# 737NG_MCDU_MainPanel_v_01.net
KiCad netlist of a schematic drawn in EasyEDA
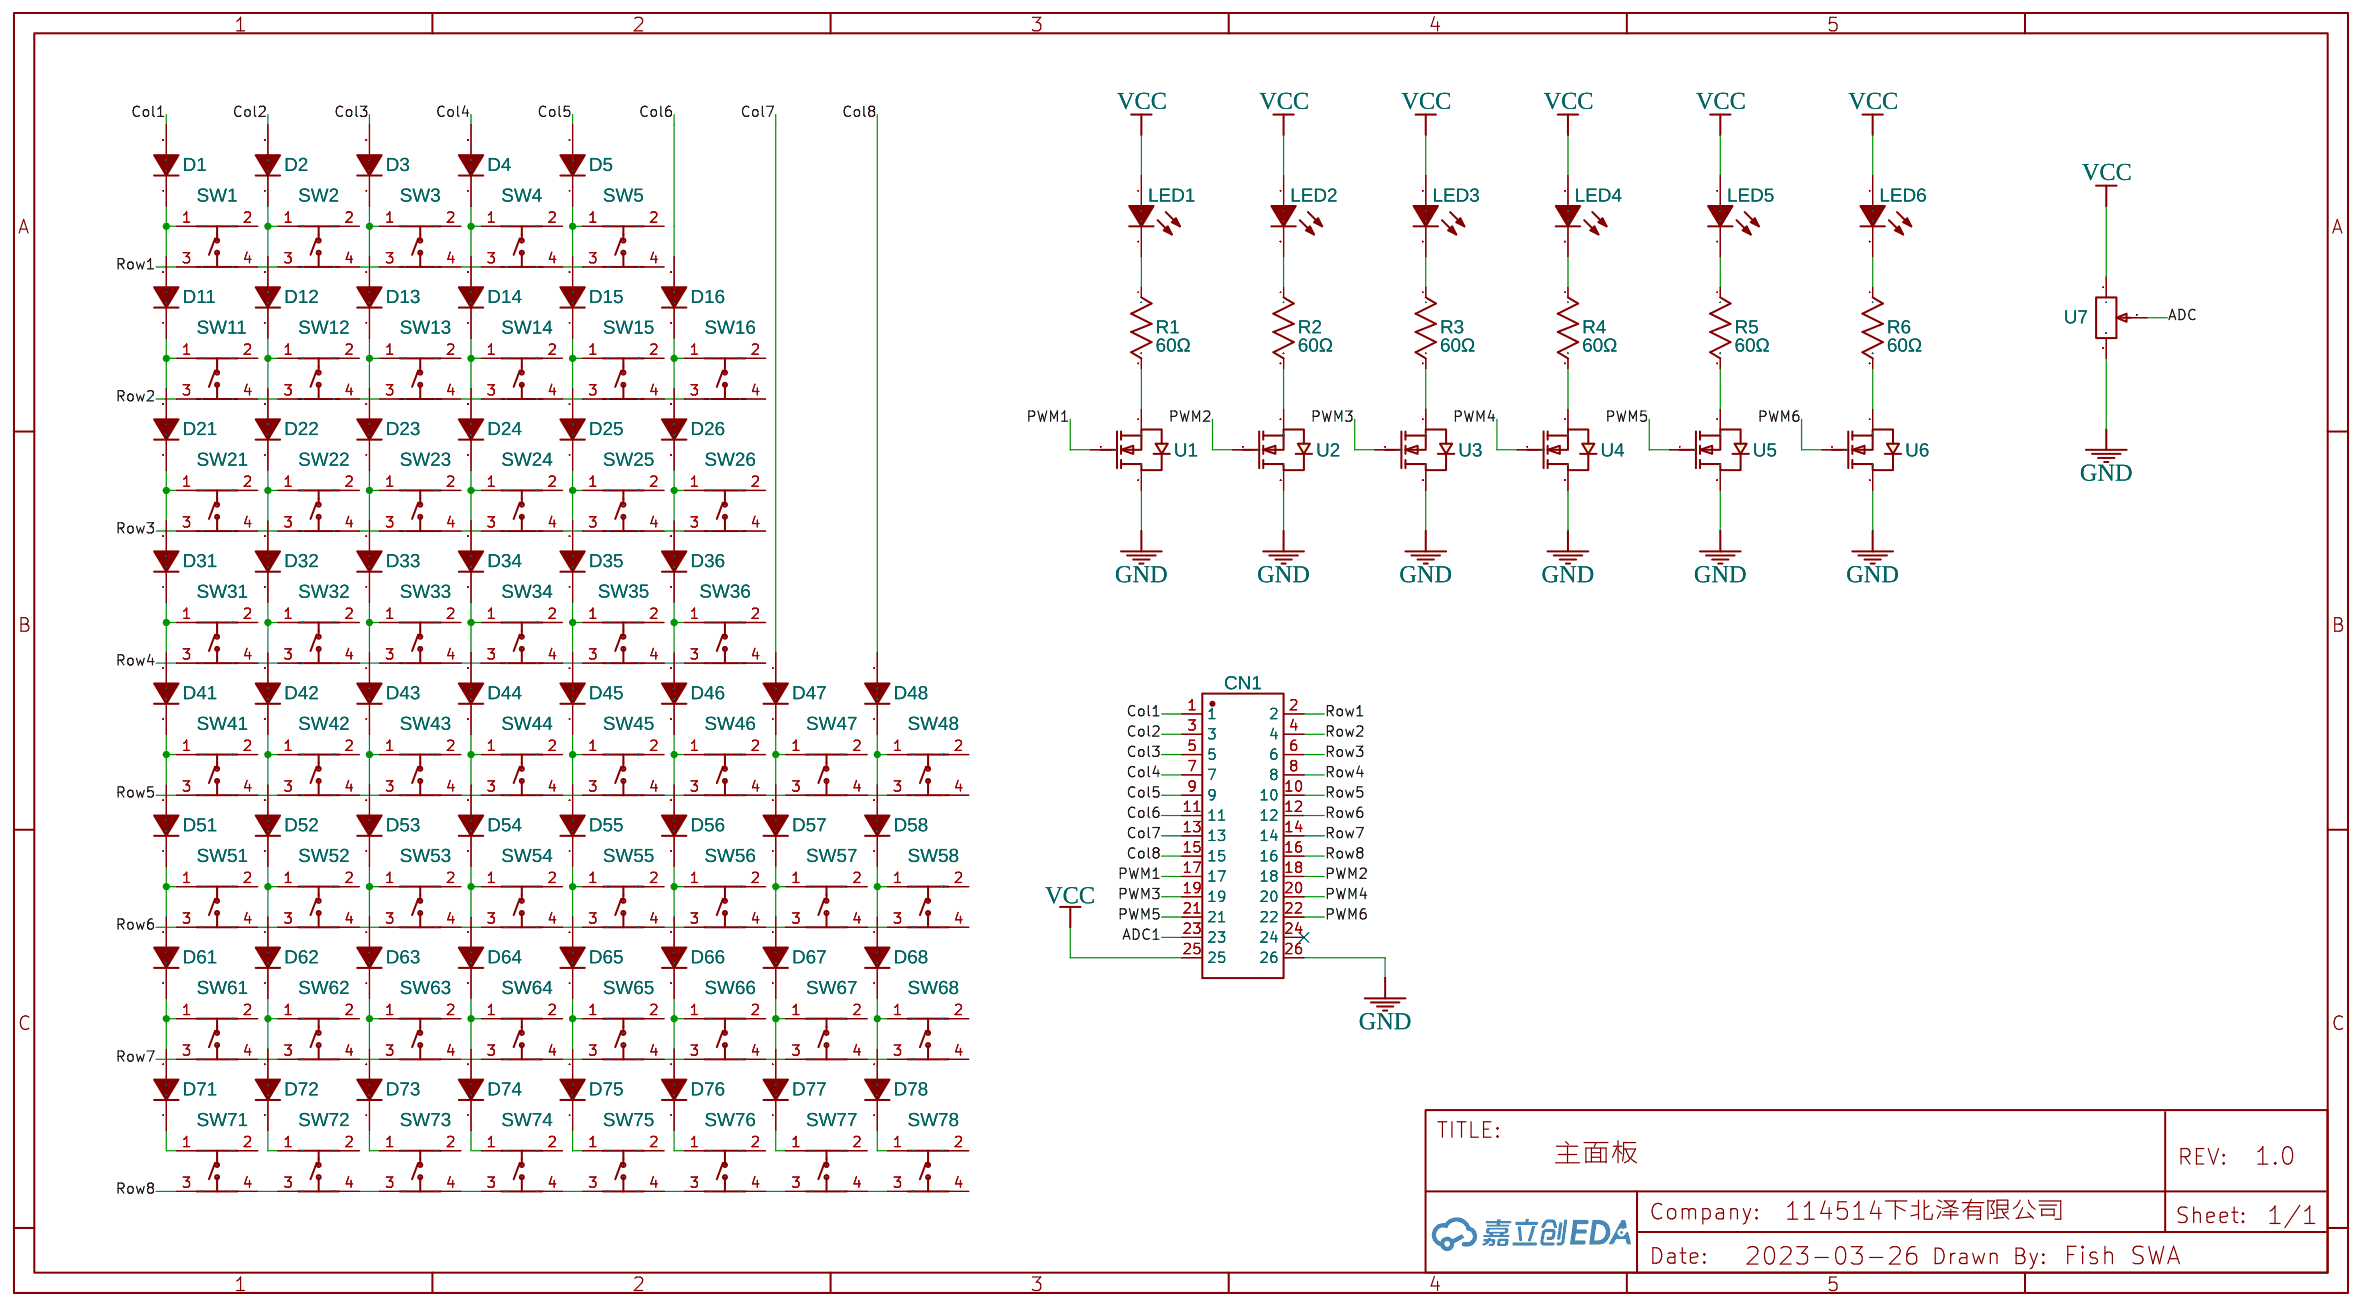
[diagram p0: schematic sheet]

(export (version "E")
  (design (tool "Eeschema 10.0.6"))
  (components
    (comp (ref "CN1")
      (value "A2004WV-2X13P")
      (fields (field (name "BOM_Supplier Part") "C465323"))
      (libsource (lib "") (part "A2004WV-2X13P"))
    )
    (comp (ref "D1")
      (value "1N4148WS T4")
      (fields (field (name "BOM_Manufacturer Part") "1N4148WS") (field (name "BOM_Supplier Part") "C2128"))
      (libsource (lib "") (part "1N4148WS T4"))
    )
    (comp (ref "D2")
      (value "1N4148WS T4")
      (fields (field (name "BOM_Manufacturer Part") "1N4148WS") (field (name "BOM_Supplier Part") "C2128"))
      (libsource (lib "") (part "1N4148WS T4"))
    )
    (comp (ref "D3")
      (value "1N4148WS T4")
      (fields (field (name "BOM_Manufacturer Part") "1N4148WS") (field (name "BOM_Supplier Part") "C2128"))
      (libsource (lib "") (part "1N4148WS T4"))
    )
    (comp (ref "D4")
      (value "1N4148WS T4")
      (fields (field (name "BOM_Manufacturer Part") "1N4148WS") (field (name "BOM_Supplier Part") "C2128"))
      (libsource (lib "") (part "1N4148WS T4"))
    )
    (comp (ref "D5")
      (value "1N4148WS T4")
      (fields (field (name "BOM_Manufacturer Part") "1N4148WS") (field (name "BOM_Supplier Part") "C2128"))
      (libsource (lib "") (part "1N4148WS T4"))
    )
    (comp (ref "D11")
      (value "1N4148WS T4")
      (fields (field (name "BOM_Manufacturer Part") "1N4148WS") (field (name "BOM_Supplier Part") "C2128"))
      (libsource (lib "") (part "1N4148WS T4"))
    )
    (comp (ref "D12")
      (value "1N4148WS T4")
      (fields (field (name "BOM_Manufacturer Part") "1N4148WS") (field (name "BOM_Supplier Part") "C2128"))
      (libsource (lib "") (part "1N4148WS T4"))
    )
    (comp (ref "D13")
      (value "1N4148WS T4")
      (fields (field (name "BOM_Manufacturer Part") "1N4148WS") (field (name "BOM_Supplier Part") "C2128"))
      (libsource (lib "") (part "1N4148WS T4"))
    )
    (comp (ref "D14")
      (value "1N4148WS T4")
      (fields (field (name "BOM_Manufacturer Part") "1N4148WS") (field (name "BOM_Supplier Part") "C2128"))
      (libsource (lib "") (part "1N4148WS T4"))
    )
    (comp (ref "D15")
      (value "1N4148WS T4")
      (fields (field (name "BOM_Manufacturer Part") "1N4148WS") (field (name "BOM_Supplier Part") "C2128"))
      (libsource (lib "") (part "1N4148WS T4"))
    )
    (comp (ref "D16")
      (value "1N4148WS T4")
      (fields (field (name "BOM_Manufacturer Part") "1N4148WS") (field (name "BOM_Supplier Part") "C2128"))
      (libsource (lib "") (part "1N4148WS T4"))
    )
    (comp (ref "D21")
      (value "1N4148WS T4")
      (fields (field (name "BOM_Manufacturer Part") "1N4148WS") (field (name "BOM_Supplier Part") "C2128"))
      (libsource (lib "") (part "1N4148WS T4"))
    )
    (comp (ref "D22")
      (value "1N4148WS T4")
      (fields (field (name "BOM_Manufacturer Part") "1N4148WS") (field (name "BOM_Supplier Part") "C2128"))
      (libsource (lib "") (part "1N4148WS T4"))
    )
    (comp (ref "D23")
      (value "1N4148WS T4")
      (fields (field (name "BOM_Manufacturer Part") "1N4148WS") (field (name "BOM_Supplier Part") "C2128"))
      (libsource (lib "") (part "1N4148WS T4"))
    )
    (comp (ref "D24")
      (value "1N4148WS T4")
      (fields (field (name "BOM_Manufacturer Part") "1N4148WS") (field (name "BOM_Supplier Part") "C2128"))
      (libsource (lib "") (part "1N4148WS T4"))
    )
    (comp (ref "D25")
      (value "1N4148WS T4")
      (fields (field (name "BOM_Manufacturer Part") "1N4148WS") (field (name "BOM_Supplier Part") "C2128"))
      (libsource (lib "") (part "1N4148WS T4"))
    )
    (comp (ref "D26")
      (value "1N4148WS T4")
      (fields (field (name "BOM_Manufacturer Part") "1N4148WS") (field (name "BOM_Supplier Part") "C2128"))
      (libsource (lib "") (part "1N4148WS T4"))
    )
    (comp (ref "D31")
      (value "1N4148WS T4")
      (fields (field (name "BOM_Manufacturer Part") "1N4148WS") (field (name "BOM_Supplier Part") "C2128"))
      (libsource (lib "") (part "1N4148WS T4"))
    )
    (comp (ref "D32")
      (value "1N4148WS T4")
      (fields (field (name "BOM_Manufacturer Part") "1N4148WS") (field (name "BOM_Supplier Part") "C2128"))
      (libsource (lib "") (part "1N4148WS T4"))
    )
    (comp (ref "D33")
      (value "1N4148WS T4")
      (fields (field (name "BOM_Manufacturer Part") "1N4148WS") (field (name "BOM_Supplier Part") "C2128"))
      (libsource (lib "") (part "1N4148WS T4"))
    )
    (comp (ref "D34")
      (value "1N4148WS T4")
      (fields (field (name "BOM_Manufacturer Part") "1N4148WS") (field (name "BOM_Supplier Part") "C2128"))
      (libsource (lib "") (part "1N4148WS T4"))
    )
    (comp (ref "D35")
      (value "1N4148WS T4")
      (fields (field (name "BOM_Manufacturer Part") "1N4148WS") (field (name "BOM_Supplier Part") "C2128"))
      (libsource (lib "") (part "1N4148WS T4"))
    )
    (comp (ref "D36")
      (value "1N4148WS T4")
      (fields (field (name "BOM_Manufacturer Part") "1N4148WS") (field (name "BOM_Supplier Part") "C2128"))
      (libsource (lib "") (part "1N4148WS T4"))
    )
    (comp (ref "D41")
      (value "1N4148WS T4")
      (fields (field (name "BOM_Manufacturer Part") "1N4148WS") (field (name "BOM_Supplier Part") "C2128"))
      (libsource (lib "") (part "1N4148WS T4"))
    )
    (comp (ref "D42")
      (value "1N4148WS T4")
      (fields (field (name "BOM_Manufacturer Part") "1N4148WS") (field (name "BOM_Supplier Part") "C2128"))
      (libsource (lib "") (part "1N4148WS T4"))
    )
    (comp (ref "D43")
      (value "1N4148WS T4")
      (fields (field (name "BOM_Manufacturer Part") "1N4148WS") (field (name "BOM_Supplier Part") "C2128"))
      (libsource (lib "") (part "1N4148WS T4"))
    )
    (comp (ref "D44")
      (value "1N4148WS T4")
      (fields (field (name "BOM_Manufacturer Part") "1N4148WS") (field (name "BOM_Supplier Part") "C2128"))
      (libsource (lib "") (part "1N4148WS T4"))
    )
    (comp (ref "D45")
      (value "1N4148WS T4")
      (fields (field (name "BOM_Manufacturer Part") "1N4148WS") (field (name "BOM_Supplier Part") "C2128"))
      (libsource (lib "") (part "1N4148WS T4"))
    )
    (comp (ref "D46")
      (value "1N4148WS T4")
      (fields (field (name "BOM_Manufacturer Part") "1N4148WS") (field (name "BOM_Supplier Part") "C2128"))
      (libsource (lib "") (part "1N4148WS T4"))
    )
    (comp (ref "D47")
      (value "1N4148WS T4")
      (fields (field (name "BOM_Manufacturer Part") "1N4148WS") (field (name "BOM_Supplier Part") "C2128"))
      (libsource (lib "") (part "1N4148WS T4"))
    )
    (comp (ref "D48")
      (value "1N4148WS T4")
      (fields (field (name "BOM_Manufacturer Part") "1N4148WS") (field (name "BOM_Supplier Part") "C2128"))
      (libsource (lib "") (part "1N4148WS T4"))
    )
    (comp (ref "D51")
      (value "1N4148WS T4")
      (fields (field (name "BOM_Manufacturer Part") "1N4148WS") (field (name "BOM_Supplier Part") "C2128"))
      (libsource (lib "") (part "1N4148WS T4"))
    )
    (comp (ref "D52")
      (value "1N4148WS T4")
      (fields (field (name "BOM_Manufacturer Part") "1N4148WS") (field (name "BOM_Supplier Part") "C2128"))
      (libsource (lib "") (part "1N4148WS T4"))
    )
    (comp (ref "D53")
      (value "1N4148WS T4")
      (fields (field (name "BOM_Manufacturer Part") "1N4148WS") (field (name "BOM_Supplier Part") "C2128"))
      (libsource (lib "") (part "1N4148WS T4"))
    )
    (comp (ref "D54")
      (value "1N4148WS T4")
      (fields (field (name "BOM_Manufacturer Part") "1N4148WS") (field (name "BOM_Supplier Part") "C2128"))
      (libsource (lib "") (part "1N4148WS T4"))
    )
    (comp (ref "D55")
      (value "1N4148WS T4")
      (fields (field (name "BOM_Manufacturer Part") "1N4148WS") (field (name "BOM_Supplier Part") "C2128"))
      (libsource (lib "") (part "1N4148WS T4"))
    )
    (comp (ref "D56")
      (value "1N4148WS T4")
      (fields (field (name "BOM_Manufacturer Part") "1N4148WS") (field (name "BOM_Supplier Part") "C2128"))
      (libsource (lib "") (part "1N4148WS T4"))
    )
    (comp (ref "D57")
      (value "1N4148WS T4")
      (fields (field (name "BOM_Manufacturer Part") "1N4148WS") (field (name "BOM_Supplier Part") "C2128"))
      (libsource (lib "") (part "1N4148WS T4"))
    )
    (comp (ref "D58")
      (value "1N4148WS T4")
      (fields (field (name "BOM_Manufacturer Part") "1N4148WS") (field (name "BOM_Supplier Part") "C2128"))
      (libsource (lib "") (part "1N4148WS T4"))
    )
    (comp (ref "D61")
      (value "1N4148WS T4")
      (fields (field (name "BOM_Manufacturer Part") "1N4148WS") (field (name "BOM_Supplier Part") "C2128"))
      (libsource (lib "") (part "1N4148WS T4"))
    )
    (comp (ref "D62")
      (value "1N4148WS T4")
      (fields (field (name "BOM_Manufacturer Part") "1N4148WS") (field (name "BOM_Supplier Part") "C2128"))
      (libsource (lib "") (part "1N4148WS T4"))
    )
    (comp (ref "D63")
      (value "1N4148WS T4")
      (fields (field (name "BOM_Manufacturer Part") "1N4148WS") (field (name "BOM_Supplier Part") "C2128"))
      (libsource (lib "") (part "1N4148WS T4"))
    )
    (comp (ref "D64")
      (value "1N4148WS T4")
      (fields (field (name "BOM_Manufacturer Part") "1N4148WS") (field (name "BOM_Supplier Part") "C2128"))
      (libsource (lib "") (part "1N4148WS T4"))
    )
    (comp (ref "D65")
      (value "1N4148WS T4")
      (fields (field (name "BOM_Manufacturer Part") "1N4148WS") (field (name "BOM_Supplier Part") "C2128"))
      (libsource (lib "") (part "1N4148WS T4"))
    )
    (comp (ref "D66")
      (value "1N4148WS T4")
      (fields (field (name "BOM_Manufacturer Part") "1N4148WS") (field (name "BOM_Supplier Part") "C2128"))
      (libsource (lib "") (part "1N4148WS T4"))
    )
    (comp (ref "D67")
      (value "1N4148WS T4")
      (fields (field (name "BOM_Manufacturer Part") "1N4148WS") (field (name "BOM_Supplier Part") "C2128"))
      (libsource (lib "") (part "1N4148WS T4"))
    )
    (comp (ref "D68")
      (value "1N4148WS T4")
      (fields (field (name "BOM_Manufacturer Part") "1N4148WS") (field (name "BOM_Supplier Part") "C2128"))
      (libsource (lib "") (part "1N4148WS T4"))
    )
    (comp (ref "D71")
      (value "1N4148WS T4")
      (fields (field (name "BOM_Manufacturer Part") "1N4148WS") (field (name "BOM_Supplier Part") "C2128"))
      (libsource (lib "") (part "1N4148WS T4"))
    )
    (comp (ref "D72")
      (value "1N4148WS T4")
      (fields (field (name "BOM_Manufacturer Part") "1N4148WS") (field (name "BOM_Supplier Part") "C2128"))
      (libsource (lib "") (part "1N4148WS T4"))
    )
    (comp (ref "D73")
      (value "1N4148WS T4")
      (fields (field (name "BOM_Manufacturer Part") "1N4148WS") (field (name "BOM_Supplier Part") "C2128"))
      (libsource (lib "") (part "1N4148WS T4"))
    )
    (comp (ref "D74")
      (value "1N4148WS T4")
      (fields (field (name "BOM_Manufacturer Part") "1N4148WS") (field (name "BOM_Supplier Part") "C2128"))
      (libsource (lib "") (part "1N4148WS T4"))
    )
    (comp (ref "D75")
      (value "1N4148WS T4")
      (fields (field (name "BOM_Manufacturer Part") "1N4148WS") (field (name "BOM_Supplier Part") "C2128"))
      (libsource (lib "") (part "1N4148WS T4"))
    )
    (comp (ref "D76")
      (value "1N4148WS T4")
      (fields (field (name "BOM_Manufacturer Part") "1N4148WS") (field (name "BOM_Supplier Part") "C2128"))
      (libsource (lib "") (part "1N4148WS T4"))
    )
    (comp (ref "D77")
      (value "1N4148WS T4")
      (fields (field (name "BOM_Manufacturer Part") "1N4148WS") (field (name "BOM_Supplier Part") "C2128"))
      (libsource (lib "") (part "1N4148WS T4"))
    )
    (comp (ref "D78")
      (value "1N4148WS T4")
      (fields (field (name "BOM_Manufacturer Part") "1N4148WS") (field (name "BOM_Supplier Part") "C2128"))
      (libsource (lib "") (part "1N4148WS T4"))
    )
    (comp (ref "LED1")
      (value "SML-H12P8TT86")
      (fields (field (name "BOM_Supplier Part") "C510035"))
      (libsource (lib "") (part "SML-H12P8TT86"))
    )
    (comp (ref "LED2")
      (value "SML-H12P8TT86")
      (fields (field (name "BOM_Supplier Part") "C510035"))
      (libsource (lib "") (part "SML-H12P8TT86"))
    )
    (comp (ref "LED3")
      (value "SML-H12P8TT86")
      (fields (field (name "BOM_Supplier Part") "C510035"))
      (libsource (lib "") (part "SML-H12P8TT86"))
    )
    (comp (ref "LED4")
      (value "SML-H12P8TT86")
      (fields (field (name "BOM_Supplier Part") "C510035"))
      (libsource (lib "") (part "SML-H12P8TT86"))
    )
    (comp (ref "LED5")
      (value "SML-H12P8TT86")
      (fields (field (name "BOM_Supplier Part") "C510035"))
      (libsource (lib "") (part "SML-H12P8TT86"))
    )
    (comp (ref "LED6")
      (value "SML-H12P8TT86")
      (fields (field (name "BOM_Supplier Part") "C510035"))
      (libsource (lib "") (part "SML-H12P8TT86"))
    )
    (comp (ref "R1") (value "60Ω") (libsource (lib "") (part "R_0805_US")))
    (comp (ref "R2") (value "60Ω") (libsource (lib "") (part "R_0805_US")))
    (comp (ref "R3") (value "60Ω") (libsource (lib "") (part "R_0805_US")))
    (comp (ref "R4") (value "60Ω") (libsource (lib "") (part "R_0805_US")))
    (comp (ref "R5") (value "60Ω") (libsource (lib "") (part "R_0805_US")))
    (comp (ref "R6") (value "60Ω") (libsource (lib "") (part "R_0805_US")))
    (comp (ref "SW1")
      (value "PTS525SM15SMTR2LFS")
      (fields (field (name "BOM_Supplier Part") "C221856"))
      (libsource (lib "") (part "PTS525SM15SMTR2LFS"))
    )
    (comp (ref "SW2")
      (value "PTS525SM15SMTR2LFS")
      (fields (field (name "BOM_Supplier Part") "C221856"))
      (libsource (lib "") (part "PTS525SM15SMTR2LFS"))
    )
    (comp (ref "SW3")
      (value "PTS525SM15SMTR2LFS")
      (fields (field (name "BOM_Supplier Part") "C221856"))
      (libsource (lib "") (part "PTS525SM15SMTR2LFS"))
    )
    (comp (ref "SW4")
      (value "PTS525SM15SMTR2LFS")
      (fields (field (name "BOM_Supplier Part") "C221856"))
      (libsource (lib "") (part "PTS525SM15SMTR2LFS"))
    )
    (comp (ref "SW5")
      (value "PTS525SM15SMTR2LFS")
      (fields (field (name "BOM_Supplier Part") "C221856"))
      (libsource (lib "") (part "PTS525SM15SMTR2LFS"))
    )
    (comp (ref "SW11")
      (value "PTS525SM15SMTR2LFS")
      (fields (field (name "BOM_Supplier Part") "C221856"))
      (libsource (lib "") (part "PTS525SM15SMTR2LFS"))
    )
    (comp (ref "SW12")
      (value "PTS525SM15SMTR2LFS")
      (fields (field (name "BOM_Supplier Part") "C221856"))
      (libsource (lib "") (part "PTS525SM15SMTR2LFS"))
    )
    (comp (ref "SW13")
      (value "PTS525SM15SMTR2LFS")
      (fields (field (name "BOM_Supplier Part") "C221856"))
      (libsource (lib "") (part "PTS525SM15SMTR2LFS"))
    )
    (comp (ref "SW14")
      (value "PTS525SM15SMTR2LFS")
      (fields (field (name "BOM_Supplier Part") "C221856"))
      (libsource (lib "") (part "PTS525SM15SMTR2LFS"))
    )
    (comp (ref "SW15")
      (value "PTS525SM15SMTR2LFS")
      (fields (field (name "BOM_Supplier Part") "C221856"))
      (libsource (lib "") (part "PTS525SM15SMTR2LFS"))
    )
    (comp (ref "SW16")
      (value "PTS525SM15SMTR2LFS")
      (fields (field (name "BOM_Supplier Part") "C221856"))
      (libsource (lib "") (part "PTS525SM15SMTR2LFS"))
    )
    (comp (ref "SW21")
      (value "PTS525SM15SMTR2LFS")
      (fields (field (name "BOM_Supplier Part") "C221856"))
      (libsource (lib "") (part "PTS525SM15SMTR2LFS"))
    )
    (comp (ref "SW22")
      (value "PTS525SM15SMTR2LFS")
      (fields (field (name "BOM_Supplier Part") "C221856"))
      (libsource (lib "") (part "PTS525SM15SMTR2LFS"))
    )
    (comp (ref "SW23")
      (value "PTS525SM15SMTR2LFS")
      (fields (field (name "BOM_Supplier Part") "C221856"))
      (libsource (lib "") (part "PTS525SM15SMTR2LFS"))
    )
    (comp (ref "SW24")
      (value "PTS525SM15SMTR2LFS")
      (fields (field (name "BOM_Supplier Part") "C221856"))
      (libsource (lib "") (part "PTS525SM15SMTR2LFS"))
    )
    (comp (ref "SW25")
      (value "PTS525SM15SMTR2LFS")
      (fields (field (name "BOM_Supplier Part") "C221856"))
      (libsource (lib "") (part "PTS525SM15SMTR2LFS"))
    )
    (comp (ref "SW26")
      (value "PTS525SM15SMTR2LFS")
      (fields (field (name "BOM_Supplier Part") "C221856"))
      (libsource (lib "") (part "PTS525SM15SMTR2LFS"))
    )
    (comp (ref "SW31")
      (value "PTS525SM15SMTR2LFS")
      (fields (field (name "BOM_Supplier Part") "C221856"))
      (libsource (lib "") (part "PTS525SM15SMTR2LFS"))
    )
    (comp (ref "SW32")
      (value "PTS525SM15SMTR2LFS")
      (fields (field (name "BOM_Supplier Part") "C221856"))
      (libsource (lib "") (part "PTS525SM15SMTR2LFS"))
    )
    (comp (ref "SW33")
      (value "PTS525SM15SMTR2LFS")
      (fields (field (name "BOM_Supplier Part") "C221856"))
      (libsource (lib "") (part "PTS525SM15SMTR2LFS"))
    )
    (comp (ref "SW34")
      (value "PTS525SM15SMTR2LFS")
      (fields (field (name "BOM_Supplier Part") "C221856"))
      (libsource (lib "") (part "PTS525SM15SMTR2LFS"))
    )
    (comp (ref "SW35")
      (value "PTS525SM15SMTR2LFS")
      (fields (field (name "BOM_Supplier Part") "C221856"))
      (libsource (lib "") (part "PTS525SM15SMTR2LFS"))
    )
    (comp (ref "SW36")
      (value "PTS525SM15SMTR2LFS")
      (fields (field (name "BOM_Supplier Part") "C221856"))
      (libsource (lib "") (part "PTS525SM15SMTR2LFS"))
    )
    (comp (ref "SW41")
      (value "PTS525SM15SMTR2LFS")
      (fields (field (name "BOM_Supplier Part") "C221856"))
      (libsource (lib "") (part "PTS525SM15SMTR2LFS"))
    )
    (comp (ref "SW42")
      (value "PTS525SM15SMTR2LFS")
      (fields (field (name "BOM_Supplier Part") "C221856"))
      (libsource (lib "") (part "PTS525SM15SMTR2LFS"))
    )
    (comp (ref "SW43")
      (value "PTS525SM15SMTR2LFS")
      (fields (field (name "BOM_Supplier Part") "C221856"))
      (libsource (lib "") (part "PTS525SM15SMTR2LFS"))
    )
    (comp (ref "SW44")
      (value "PTS525SM15SMTR2LFS")
      (fields (field (name "BOM_Supplier Part") "C221856"))
      (libsource (lib "") (part "PTS525SM15SMTR2LFS"))
    )
    (comp (ref "SW45")
      (value "PTS525SM15SMTR2LFS")
      (fields (field (name "BOM_Supplier Part") "C221856"))
      (libsource (lib "") (part "PTS525SM15SMTR2LFS"))
    )
    (comp (ref "SW46")
      (value "PTS525SM15SMTR2LFS")
      (fields (field (name "BOM_Supplier Part") "C221856"))
      (libsource (lib "") (part "PTS525SM15SMTR2LFS"))
    )
    (comp (ref "SW47")
      (value "PTS525SM15SMTR2LFS")
      (fields (field (name "BOM_Supplier Part") "C221856"))
      (libsource (lib "") (part "PTS525SM15SMTR2LFS"))
    )
    (comp (ref "SW48")
      (value "PTS525SM15SMTR2LFS")
      (fields (field (name "BOM_Supplier Part") "C221856"))
      (libsource (lib "") (part "PTS525SM15SMTR2LFS"))
    )
    (comp (ref "SW51")
      (value "PTS525SM15SMTR2LFS")
      (fields (field (name "BOM_Supplier Part") "C221856"))
      (libsource (lib "") (part "PTS525SM15SMTR2LFS"))
    )
    (comp (ref "SW52")
      (value "PTS525SM15SMTR2LFS")
      (fields (field (name "BOM_Supplier Part") "C221856"))
      (libsource (lib "") (part "PTS525SM15SMTR2LFS"))
    )
    (comp (ref "SW53")
      (value "PTS525SM15SMTR2LFS")
      (fields (field (name "BOM_Supplier Part") "C221856"))
      (libsource (lib "") (part "PTS525SM15SMTR2LFS"))
    )
    (comp (ref "SW54")
      (value "PTS525SM15SMTR2LFS")
      (fields (field (name "BOM_Supplier Part") "C221856"))
      (libsource (lib "") (part "PTS525SM15SMTR2LFS"))
    )
    (comp (ref "SW55")
      (value "PTS525SM15SMTR2LFS")
      (fields (field (name "BOM_Supplier Part") "C221856"))
      (libsource (lib "") (part "PTS525SM15SMTR2LFS"))
    )
    (comp (ref "SW56")
      (value "PTS525SM15SMTR2LFS")
      (fields (field (name "BOM_Supplier Part") "C221856"))
      (libsource (lib "") (part "PTS525SM15SMTR2LFS"))
    )
    (comp (ref "SW57")
      (value "PTS525SM15SMTR2LFS")
      (fields (field (name "BOM_Supplier Part") "C221856"))
      (libsource (lib "") (part "PTS525SM15SMTR2LFS"))
    )
    (comp (ref "SW58")
      (value "PTS525SM15SMTR2LFS")
      (fields (field (name "BOM_Supplier Part") "C221856"))
      (libsource (lib "") (part "PTS525SM15SMTR2LFS"))
    )
    (comp (ref "SW61")
      (value "PTS525SM15SMTR2LFS")
      (fields (field (name "BOM_Supplier Part") "C221856"))
      (libsource (lib "") (part "PTS525SM15SMTR2LFS"))
    )
    (comp (ref "SW62")
      (value "PTS525SM15SMTR2LFS")
      (fields (field (name "BOM_Supplier Part") "C221856"))
      (libsource (lib "") (part "PTS525SM15SMTR2LFS"))
    )
    (comp (ref "SW63")
      (value "PTS525SM15SMTR2LFS")
      (fields (field (name "BOM_Supplier Part") "C221856"))
      (libsource (lib "") (part "PTS525SM15SMTR2LFS"))
    )
    (comp (ref "SW64")
      (value "PTS525SM15SMTR2LFS")
      (fields (field (name "BOM_Supplier Part") "C221856"))
      (libsource (lib "") (part "PTS525SM15SMTR2LFS"))
    )
    (comp (ref "SW65")
      (value "PTS525SM15SMTR2LFS")
      (fields (field (name "BOM_Supplier Part") "C221856"))
      (libsource (lib "") (part "PTS525SM15SMTR2LFS"))
    )
    (comp (ref "SW66")
      (value "PTS525SM15SMTR2LFS")
      (fields (field (name "BOM_Supplier Part") "C221856"))
      (libsource (lib "") (part "PTS525SM15SMTR2LFS"))
    )
    (comp (ref "SW67")
      (value "PTS525SM15SMTR2LFS")
      (fields (field (name "BOM_Supplier Part") "C221856"))
      (libsource (lib "") (part "PTS525SM15SMTR2LFS"))
    )
    (comp (ref "SW68")
      (value "PTS525SM15SMTR2LFS")
      (fields (field (name "BOM_Supplier Part") "C221856"))
      (libsource (lib "") (part "PTS525SM15SMTR2LFS"))
    )
    (comp (ref "SW71")
      (value "PTS525SM15SMTR2LFS")
      (fields (field (name "BOM_Supplier Part") "C221856"))
      (libsource (lib "") (part "PTS525SM15SMTR2LFS"))
    )
    (comp (ref "SW72")
      (value "PTS525SM15SMTR2LFS")
      (fields (field (name "BOM_Supplier Part") "C221856"))
      (libsource (lib "") (part "PTS525SM15SMTR2LFS"))
    )
    (comp (ref "SW73")
      (value "PTS525SM15SMTR2LFS")
      (fields (field (name "BOM_Supplier Part") "C221856"))
      (libsource (lib "") (part "PTS525SM15SMTR2LFS"))
    )
    (comp (ref "SW74")
      (value "PTS525SM15SMTR2LFS")
      (fields (field (name "BOM_Supplier Part") "C221856"))
      (libsource (lib "") (part "PTS525SM15SMTR2LFS"))
    )
    (comp (ref "SW75")
      (value "PTS525SM15SMTR2LFS")
      (fields (field (name "BOM_Supplier Part") "C221856"))
      (libsource (lib "") (part "PTS525SM15SMTR2LFS"))
    )
    (comp (ref "SW76")
      (value "PTS525SM15SMTR2LFS")
      (fields (field (name "BOM_Supplier Part") "C221856"))
      (libsource (lib "") (part "PTS525SM15SMTR2LFS"))
    )
    (comp (ref "SW77")
      (value "PTS525SM15SMTR2LFS")
      (fields (field (name "BOM_Supplier Part") "C221856"))
      (libsource (lib "") (part "PTS525SM15SMTR2LFS"))
    )
    (comp (ref "SW78")
      (value "PTS525SM15SMTR2LFS")
      (fields (field (name "BOM_Supplier Part") "C221856"))
      (libsource (lib "") (part "PTS525SM15SMTR2LFS"))
    )
    (comp (ref "U1")
      (value "5N10_C5140036")
      (fields (field (name "BOM_Manufacturer Part") "5N10-MS") (field (name "BOM_Supplier Part") "C5140036"))
      (libsource (lib "") (part "5N10_C5140036"))
    )
    (comp (ref "U2")
      (value "5N10_C5140036")
      (fields (field (name "BOM_Manufacturer Part") "5N10-MS") (field (name "BOM_Supplier Part") "C5140036"))
      (libsource (lib "") (part "5N10_C5140036"))
    )
    (comp (ref "U3")
      (value "5N10_C5140036")
      (fields (field (name "BOM_Manufacturer Part") "5N10-MS") (field (name "BOM_Supplier Part") "C5140036"))
      (libsource (lib "") (part "5N10_C5140036"))
    )
    (comp (ref "U4")
      (value "5N10_C5140036")
      (fields (field (name "BOM_Manufacturer Part") "5N10-MS") (field (name "BOM_Supplier Part") "C5140036"))
      (libsource (lib "") (part "5N10_C5140036"))
    )
    (comp (ref "U5")
      (value "5N10_C5140036")
      (fields (field (name "BOM_Manufacturer Part") "5N10-MS") (field (name "BOM_Supplier Part") "C5140036"))
      (libsource (lib "") (part "5N10_C5140036"))
    )
    (comp (ref "U6")
      (value "5N10_C5140036")
      (fields (field (name "BOM_Manufacturer Part") "5N10-MS") (field (name "BOM_Supplier Part") "C5140036"))
      (libsource (lib "") (part "5N10_C5140036"))
    )
    (comp (ref "U7")
      (value "WH06-2C-203(20K)")
      (fields (field (name "BOM_Supplier Part") "C5205044"))
      (libsource (lib "") (part "WH06-2C-203(20K)"))
    )
  )
  (nets
    (net (code "1") (name "/ADC") (class "Default")
      (node (ref "U7") (pin "2") (pinfunction "2_2") (pintype "input"))
    )
    (net (code "2") (name "/ADC1") (class "Default")
      (node (ref "CN1") (pin "23") (pinfunction "23_23") (pintype "unspecified"))
    )
    (net (code "3") (name "/Col1") (class "Default")
      (node (ref "CN1") (pin "1") (pinfunction "1_1") (pintype "unspecified"))
      (node (ref "D1") (pin "2") (pinfunction "A_2") (pintype "unspecified"))
    )
    (net (code "4") (name "/Col2") (class "Default")
      (node (ref "CN1") (pin "3") (pinfunction "3_3") (pintype "unspecified"))
      (node (ref "D2") (pin "2") (pinfunction "A_2") (pintype "unspecified"))
    )
    (net (code "5") (name "/Col3") (class "Default")
      (node (ref "CN1") (pin "5") (pinfunction "5_5") (pintype "unspecified"))
      (node (ref "D3") (pin "2") (pinfunction "A_2") (pintype "unspecified"))
    )
    (net (code "6") (name "/Col4") (class "Default")
      (node (ref "CN1") (pin "7") (pinfunction "7_7") (pintype "unspecified"))
      (node (ref "D4") (pin "2") (pinfunction "A_2") (pintype "unspecified"))
    )
    (net (code "7") (name "/Col5") (class "Default")
      (node (ref "CN1") (pin "9") (pinfunction "9_9") (pintype "unspecified"))
      (node (ref "D5") (pin "2") (pinfunction "A_2") (pintype "unspecified"))
    )
    (net (code "8") (name "/Col6") (class "Default")
      (node (ref "CN1") (pin "11") (pinfunction "11_11") (pintype "unspecified"))
      (node (ref "D16") (pin "2") (pinfunction "A_2") (pintype "unspecified"))
    )
    (net (code "9") (name "/Col7") (class "Default")
      (node (ref "CN1") (pin "13") (pinfunction "13_13") (pintype "unspecified"))
      (node (ref "D47") (pin "2") (pinfunction "A_2") (pintype "unspecified"))
    )
    (net (code "10") (name "/Col8") (class "Default")
      (node (ref "CN1") (pin "15") (pinfunction "15_15") (pintype "unspecified"))
      (node (ref "D48") (pin "2") (pinfunction "A_2") (pintype "unspecified"))
    )
    (net (code "11") (name "/PWM1") (class "Default")
      (node (ref "CN1") (pin "17") (pinfunction "17_17") (pintype "unspecified"))
      (node (ref "U1") (pin "1") (pinfunction "G_1") (pintype "unspecified"))
    )
    (net (code "12") (name "/PWM2") (class "Default")
      (node (ref "CN1") (pin "18") (pinfunction "18_18") (pintype "unspecified"))
      (node (ref "U2") (pin "1") (pinfunction "G_1") (pintype "unspecified"))
    )
    (net (code "13") (name "/PWM3") (class "Default")
      (node (ref "CN1") (pin "19") (pinfunction "19_19") (pintype "unspecified"))
      (node (ref "U3") (pin "1") (pinfunction "G_1") (pintype "unspecified"))
    )
    (net (code "14") (name "/PWM4") (class "Default")
      (node (ref "CN1") (pin "20") (pinfunction "20_20") (pintype "unspecified"))
      (node (ref "U4") (pin "1") (pinfunction "G_1") (pintype "unspecified"))
    )
    (net (code "15") (name "/PWM5") (class "Default")
      (node (ref "CN1") (pin "21") (pinfunction "21_21") (pintype "unspecified"))
      (node (ref "U5") (pin "1") (pinfunction "G_1") (pintype "unspecified"))
    )
    (net (code "16") (name "/PWM6") (class "Default")
      (node (ref "CN1") (pin "22") (pinfunction "22_22") (pintype "unspecified"))
      (node (ref "U6") (pin "1") (pinfunction "G_1") (pintype "unspecified"))
    )
    (net (code "17") (name "/Row1") (class "Default")
      (node (ref "CN1") (pin "2") (pinfunction "2_2") (pintype "unspecified"))
      (node (ref "SW1") (pin "3") (pinfunction "3_3") (pintype "unspecified"))
    )
    (net (code "18") (name "/Row2") (class "Default")
      (node (ref "CN1") (pin "4") (pinfunction "4_4") (pintype "unspecified"))
      (node (ref "SW11") (pin "3") (pinfunction "3_3") (pintype "unspecified"))
    )
    (net (code "19") (name "/Row3") (class "Default")
      (node (ref "CN1") (pin "6") (pinfunction "6_6") (pintype "unspecified"))
      (node (ref "SW21") (pin "3") (pinfunction "3_3") (pintype "unspecified"))
    )
    (net (code "20") (name "/Row4") (class "Default")
      (node (ref "CN1") (pin "8") (pinfunction "8_8") (pintype "unspecified"))
      (node (ref "SW31") (pin "3") (pinfunction "3_3") (pintype "unspecified"))
    )
    (net (code "21") (name "/Row5") (class "Default")
      (node (ref "CN1") (pin "10") (pinfunction "10_10") (pintype "unspecified"))
      (node (ref "SW41") (pin "3") (pinfunction "3_3") (pintype "unspecified"))
    )
    (net (code "22") (name "/Row6") (class "Default")
      (node (ref "CN1") (pin "12") (pinfunction "12_12") (pintype "unspecified"))
      (node (ref "SW51") (pin "3") (pinfunction "3_3") (pintype "unspecified"))
    )
    (net (code "23") (name "/Row7") (class "Default")
      (node (ref "CN1") (pin "14") (pinfunction "14_14") (pintype "unspecified"))
      (node (ref "SW61") (pin "3") (pinfunction "3_3") (pintype "unspecified"))
    )
    (net (code "24") (name "/Row8") (class "Default")
      (node (ref "CN1") (pin "16") (pinfunction "16_16") (pintype "unspecified"))
      (node (ref "SW71") (pin "3") (pinfunction "3_3") (pintype "unspecified"))
    )
    (net (code "25") (name "GND") (class "Default")
      (node (ref "CN1") (pin "26") (pinfunction "26_26") (pintype "unspecified"))
      (node (ref "U1") (pin "3") (pinfunction "D_3") (pintype "unspecified"))
      (node (ref "U2") (pin "3") (pinfunction "D_3") (pintype "unspecified"))
      (node (ref "U3") (pin "3") (pinfunction "D_3") (pintype "unspecified"))
      (node (ref "U4") (pin "3") (pinfunction "D_3") (pintype "unspecified"))
      (node (ref "U5") (pin "3") (pinfunction "D_3") (pintype "unspecified"))
      (node (ref "U6") (pin "3") (pinfunction "D_3") (pintype "unspecified"))
      (node (ref "U7") (pin "3") (pinfunction "3_3") (pintype "input"))
    )
    (net (code "26") (name "Net-(D1-K)") (class "Default")
      (node (ref "D1") (pin "1") (pinfunction "K_1") (pintype "unspecified"))
      (node (ref "D11") (pin "2") (pinfunction "A_2") (pintype "unspecified"))
      (node (ref "SW1") (pin "1") (pinfunction "1_1") (pintype "unspecified"))
    )
    (net (code "27") (name "Net-(D11-K)") (class "Default")
      (node (ref "D11") (pin "1") (pinfunction "K_1") (pintype "unspecified"))
      (node (ref "D21") (pin "2") (pinfunction "A_2") (pintype "unspecified"))
      (node (ref "SW11") (pin "1") (pinfunction "1_1") (pintype "unspecified"))
    )
    (net (code "28") (name "Net-(D12-A)") (class "Default")
      (node (ref "D12") (pin "2") (pinfunction "A_2") (pintype "unspecified"))
      (node (ref "D2") (pin "1") (pinfunction "K_1") (pintype "unspecified"))
      (node (ref "SW2") (pin "1") (pinfunction "1_1") (pintype "unspecified"))
    )
    (net (code "29") (name "Net-(D12-K)") (class "Default")
      (node (ref "D12") (pin "1") (pinfunction "K_1") (pintype "unspecified"))
      (node (ref "D22") (pin "2") (pinfunction "A_2") (pintype "unspecified"))
      (node (ref "SW12") (pin "1") (pinfunction "1_1") (pintype "unspecified"))
    )
    (net (code "30") (name "Net-(D13-A)") (class "Default")
      (node (ref "D13") (pin "2") (pinfunction "A_2") (pintype "unspecified"))
      (node (ref "D3") (pin "1") (pinfunction "K_1") (pintype "unspecified"))
      (node (ref "SW3") (pin "1") (pinfunction "1_1") (pintype "unspecified"))
    )
    (net (code "31") (name "Net-(D13-K)") (class "Default")
      (node (ref "D13") (pin "1") (pinfunction "K_1") (pintype "unspecified"))
      (node (ref "D23") (pin "2") (pinfunction "A_2") (pintype "unspecified"))
      (node (ref "SW13") (pin "1") (pinfunction "1_1") (pintype "unspecified"))
    )
    (net (code "32") (name "Net-(D14-A)") (class "Default")
      (node (ref "D14") (pin "2") (pinfunction "A_2") (pintype "unspecified"))
      (node (ref "D4") (pin "1") (pinfunction "K_1") (pintype "unspecified"))
      (node (ref "SW4") (pin "1") (pinfunction "1_1") (pintype "unspecified"))
    )
    (net (code "33") (name "Net-(D14-K)") (class "Default")
      (node (ref "D14") (pin "1") (pinfunction "K_1") (pintype "unspecified"))
      (node (ref "D24") (pin "2") (pinfunction "A_2") (pintype "unspecified"))
      (node (ref "SW14") (pin "1") (pinfunction "1_1") (pintype "unspecified"))
    )
    (net (code "34") (name "Net-(D15-A)") (class "Default")
      (node (ref "D15") (pin "2") (pinfunction "A_2") (pintype "unspecified"))
      (node (ref "D5") (pin "1") (pinfunction "K_1") (pintype "unspecified"))
      (node (ref "SW5") (pin "1") (pinfunction "1_1") (pintype "unspecified"))
    )
    (net (code "35") (name "Net-(D15-K)") (class "Default")
      (node (ref "D15") (pin "1") (pinfunction "K_1") (pintype "unspecified"))
      (node (ref "D25") (pin "2") (pinfunction "A_2") (pintype "unspecified"))
      (node (ref "SW15") (pin "1") (pinfunction "1_1") (pintype "unspecified"))
    )
    (net (code "36") (name "Net-(D16-K)") (class "Default")
      (node (ref "D16") (pin "1") (pinfunction "K_1") (pintype "unspecified"))
      (node (ref "D26") (pin "2") (pinfunction "A_2") (pintype "unspecified"))
      (node (ref "SW16") (pin "1") (pinfunction "1_1") (pintype "unspecified"))
    )
    (net (code "37") (name "Net-(D21-K)") (class "Default")
      (node (ref "D21") (pin "1") (pinfunction "K_1") (pintype "unspecified"))
      (node (ref "D31") (pin "2") (pinfunction "A_2") (pintype "unspecified"))
      (node (ref "SW21") (pin "1") (pinfunction "1_1") (pintype "unspecified"))
    )
    (net (code "38") (name "Net-(D22-K)") (class "Default")
      (node (ref "D22") (pin "1") (pinfunction "K_1") (pintype "unspecified"))
      (node (ref "D32") (pin "2") (pinfunction "A_2") (pintype "unspecified"))
      (node (ref "SW22") (pin "1") (pinfunction "1_1") (pintype "unspecified"))
    )
    (net (code "39") (name "Net-(D23-K)") (class "Default")
      (node (ref "D23") (pin "1") (pinfunction "K_1") (pintype "unspecified"))
      (node (ref "D33") (pin "2") (pinfunction "A_2") (pintype "unspecified"))
      (node (ref "SW23") (pin "1") (pinfunction "1_1") (pintype "unspecified"))
    )
    (net (code "40") (name "Net-(D24-K)") (class "Default")
      (node (ref "D24") (pin "1") (pinfunction "K_1") (pintype "unspecified"))
      (node (ref "D34") (pin "2") (pinfunction "A_2") (pintype "unspecified"))
      (node (ref "SW24") (pin "1") (pinfunction "1_1") (pintype "unspecified"))
    )
    (net (code "41") (name "Net-(D25-K)") (class "Default")
      (node (ref "D25") (pin "1") (pinfunction "K_1") (pintype "unspecified"))
      (node (ref "D35") (pin "2") (pinfunction "A_2") (pintype "unspecified"))
      (node (ref "SW25") (pin "1") (pinfunction "1_1") (pintype "unspecified"))
    )
    (net (code "42") (name "Net-(D26-K)") (class "Default")
      (node (ref "D26") (pin "1") (pinfunction "K_1") (pintype "unspecified"))
      (node (ref "D36") (pin "2") (pinfunction "A_2") (pintype "unspecified"))
      (node (ref "SW26") (pin "1") (pinfunction "1_1") (pintype "unspecified"))
    )
    (net (code "43") (name "Net-(D31-K)") (class "Default")
      (node (ref "D31") (pin "1") (pinfunction "K_1") (pintype "unspecified"))
      (node (ref "D41") (pin "2") (pinfunction "A_2") (pintype "unspecified"))
      (node (ref "SW31") (pin "1") (pinfunction "1_1") (pintype "unspecified"))
    )
    (net (code "44") (name "Net-(D32-K)") (class "Default")
      (node (ref "D32") (pin "1") (pinfunction "K_1") (pintype "unspecified"))
      (node (ref "D42") (pin "2") (pinfunction "A_2") (pintype "unspecified"))
      (node (ref "SW32") (pin "1") (pinfunction "1_1") (pintype "unspecified"))
    )
    (net (code "45") (name "Net-(D33-K)") (class "Default")
      (node (ref "D33") (pin "1") (pinfunction "K_1") (pintype "unspecified"))
      (node (ref "D43") (pin "2") (pinfunction "A_2") (pintype "unspecified"))
      (node (ref "SW33") (pin "1") (pinfunction "1_1") (pintype "unspecified"))
    )
    (net (code "46") (name "Net-(D34-K)") (class "Default")
      (node (ref "D34") (pin "1") (pinfunction "K_1") (pintype "unspecified"))
      (node (ref "D44") (pin "2") (pinfunction "A_2") (pintype "unspecified"))
      (node (ref "SW34") (pin "1") (pinfunction "1_1") (pintype "unspecified"))
    )
    (net (code "47") (name "Net-(D35-K)") (class "Default")
      (node (ref "D35") (pin "1") (pinfunction "K_1") (pintype "unspecified"))
      (node (ref "D45") (pin "2") (pinfunction "A_2") (pintype "unspecified"))
      (node (ref "SW35") (pin "1") (pinfunction "1_1") (pintype "unspecified"))
    )
    (net (code "48") (name "Net-(D36-K)") (class "Default")
      (node (ref "D36") (pin "1") (pinfunction "K_1") (pintype "unspecified"))
      (node (ref "D46") (pin "2") (pinfunction "A_2") (pintype "unspecified"))
      (node (ref "SW36") (pin "1") (pinfunction "1_1") (pintype "unspecified"))
    )
    (net (code "49") (name "Net-(D41-K)") (class "Default")
      (node (ref "D41") (pin "1") (pinfunction "K_1") (pintype "unspecified"))
      (node (ref "D51") (pin "2") (pinfunction "A_2") (pintype "unspecified"))
      (node (ref "SW41") (pin "1") (pinfunction "1_1") (pintype "unspecified"))
    )
    (net (code "50") (name "Net-(D42-K)") (class "Default")
      (node (ref "D42") (pin "1") (pinfunction "K_1") (pintype "unspecified"))
      (node (ref "D52") (pin "2") (pinfunction "A_2") (pintype "unspecified"))
      (node (ref "SW42") (pin "1") (pinfunction "1_1") (pintype "unspecified"))
    )
    (net (code "51") (name "Net-(D43-K)") (class "Default")
      (node (ref "D43") (pin "1") (pinfunction "K_1") (pintype "unspecified"))
      (node (ref "D53") (pin "2") (pinfunction "A_2") (pintype "unspecified"))
      (node (ref "SW43") (pin "1") (pinfunction "1_1") (pintype "unspecified"))
    )
    (net (code "52") (name "Net-(D44-K)") (class "Default")
      (node (ref "D44") (pin "1") (pinfunction "K_1") (pintype "unspecified"))
      (node (ref "D54") (pin "2") (pinfunction "A_2") (pintype "unspecified"))
      (node (ref "SW44") (pin "1") (pinfunction "1_1") (pintype "unspecified"))
    )
    (net (code "53") (name "Net-(D45-K)") (class "Default")
      (node (ref "D45") (pin "1") (pinfunction "K_1") (pintype "unspecified"))
      (node (ref "D55") (pin "2") (pinfunction "A_2") (pintype "unspecified"))
      (node (ref "SW45") (pin "1") (pinfunction "1_1") (pintype "unspecified"))
    )
    (net (code "54") (name "Net-(D46-K)") (class "Default")
      (node (ref "D46") (pin "1") (pinfunction "K_1") (pintype "unspecified"))
      (node (ref "D56") (pin "2") (pinfunction "A_2") (pintype "unspecified"))
      (node (ref "SW46") (pin "1") (pinfunction "1_1") (pintype "unspecified"))
    )
    (net (code "55") (name "Net-(D47-K)") (class "Default")
      (node (ref "D47") (pin "1") (pinfunction "K_1") (pintype "unspecified"))
      (node (ref "D57") (pin "2") (pinfunction "A_2") (pintype "unspecified"))
      (node (ref "SW47") (pin "1") (pinfunction "1_1") (pintype "unspecified"))
    )
    (net (code "56") (name "Net-(D48-K)") (class "Default")
      (node (ref "D48") (pin "1") (pinfunction "K_1") (pintype "unspecified"))
      (node (ref "D58") (pin "2") (pinfunction "A_2") (pintype "unspecified"))
      (node (ref "SW48") (pin "1") (pinfunction "1_1") (pintype "unspecified"))
    )
    (net (code "57") (name "Net-(D51-K)") (class "Default")
      (node (ref "D51") (pin "1") (pinfunction "K_1") (pintype "unspecified"))
      (node (ref "D61") (pin "2") (pinfunction "A_2") (pintype "unspecified"))
      (node (ref "SW51") (pin "1") (pinfunction "1_1") (pintype "unspecified"))
    )
    (net (code "58") (name "Net-(D52-K)") (class "Default")
      (node (ref "D52") (pin "1") (pinfunction "K_1") (pintype "unspecified"))
      (node (ref "D62") (pin "2") (pinfunction "A_2") (pintype "unspecified"))
      (node (ref "SW52") (pin "1") (pinfunction "1_1") (pintype "unspecified"))
    )
    (net (code "59") (name "Net-(D53-K)") (class "Default")
      (node (ref "D53") (pin "1") (pinfunction "K_1") (pintype "unspecified"))
      (node (ref "D63") (pin "2") (pinfunction "A_2") (pintype "unspecified"))
      (node (ref "SW53") (pin "1") (pinfunction "1_1") (pintype "unspecified"))
    )
    (net (code "60") (name "Net-(D54-K)") (class "Default")
      (node (ref "D54") (pin "1") (pinfunction "K_1") (pintype "unspecified"))
      (node (ref "D64") (pin "2") (pinfunction "A_2") (pintype "unspecified"))
      (node (ref "SW54") (pin "1") (pinfunction "1_1") (pintype "unspecified"))
    )
    (net (code "61") (name "Net-(D55-K)") (class "Default")
      (node (ref "D55") (pin "1") (pinfunction "K_1") (pintype "unspecified"))
      (node (ref "D65") (pin "2") (pinfunction "A_2") (pintype "unspecified"))
      (node (ref "SW55") (pin "1") (pinfunction "1_1") (pintype "unspecified"))
    )
    (net (code "62") (name "Net-(D56-K)") (class "Default")
      (node (ref "D56") (pin "1") (pinfunction "K_1") (pintype "unspecified"))
      (node (ref "D66") (pin "2") (pinfunction "A_2") (pintype "unspecified"))
      (node (ref "SW56") (pin "1") (pinfunction "1_1") (pintype "unspecified"))
    )
    (net (code "63") (name "Net-(D57-K)") (class "Default")
      (node (ref "D57") (pin "1") (pinfunction "K_1") (pintype "unspecified"))
      (node (ref "D67") (pin "2") (pinfunction "A_2") (pintype "unspecified"))
      (node (ref "SW57") (pin "1") (pinfunction "1_1") (pintype "unspecified"))
    )
    (net (code "64") (name "Net-(D58-K)") (class "Default")
      (node (ref "D58") (pin "1") (pinfunction "K_1") (pintype "unspecified"))
      (node (ref "D68") (pin "2") (pinfunction "A_2") (pintype "unspecified"))
      (node (ref "SW58") (pin "1") (pinfunction "1_1") (pintype "unspecified"))
    )
    (net (code "65") (name "Net-(D61-K)") (class "Default")
      (node (ref "D61") (pin "1") (pinfunction "K_1") (pintype "unspecified"))
      (node (ref "D71") (pin "2") (pinfunction "A_2") (pintype "unspecified"))
      (node (ref "SW61") (pin "1") (pinfunction "1_1") (pintype "unspecified"))
    )
    (net (code "66") (name "Net-(D62-K)") (class "Default")
      (node (ref "D62") (pin "1") (pinfunction "K_1") (pintype "unspecified"))
      (node (ref "D72") (pin "2") (pinfunction "A_2") (pintype "unspecified"))
      (node (ref "SW62") (pin "1") (pinfunction "1_1") (pintype "unspecified"))
    )
    (net (code "67") (name "Net-(D63-K)") (class "Default")
      (node (ref "D63") (pin "1") (pinfunction "K_1") (pintype "unspecified"))
      (node (ref "D73") (pin "2") (pinfunction "A_2") (pintype "unspecified"))
      (node (ref "SW63") (pin "1") (pinfunction "1_1") (pintype "unspecified"))
    )
    (net (code "68") (name "Net-(D64-K)") (class "Default")
      (node (ref "D64") (pin "1") (pinfunction "K_1") (pintype "unspecified"))
      (node (ref "D74") (pin "2") (pinfunction "A_2") (pintype "unspecified"))
      (node (ref "SW64") (pin "1") (pinfunction "1_1") (pintype "unspecified"))
    )
    (net (code "69") (name "Net-(D65-K)") (class "Default")
      (node (ref "D65") (pin "1") (pinfunction "K_1") (pintype "unspecified"))
      (node (ref "D75") (pin "2") (pinfunction "A_2") (pintype "unspecified"))
      (node (ref "SW65") (pin "1") (pinfunction "1_1") (pintype "unspecified"))
    )
    (net (code "70") (name "Net-(D66-K)") (class "Default")
      (node (ref "D66") (pin "1") (pinfunction "K_1") (pintype "unspecified"))
      (node (ref "D76") (pin "2") (pinfunction "A_2") (pintype "unspecified"))
      (node (ref "SW66") (pin "1") (pinfunction "1_1") (pintype "unspecified"))
    )
    (net (code "71") (name "Net-(D67-K)") (class "Default")
      (node (ref "D67") (pin "1") (pinfunction "K_1") (pintype "unspecified"))
      (node (ref "D77") (pin "2") (pinfunction "A_2") (pintype "unspecified"))
      (node (ref "SW67") (pin "1") (pinfunction "1_1") (pintype "unspecified"))
    )
    (net (code "72") (name "Net-(D68-K)") (class "Default")
      (node (ref "D68") (pin "1") (pinfunction "K_1") (pintype "unspecified"))
      (node (ref "D78") (pin "2") (pinfunction "A_2") (pintype "unspecified"))
      (node (ref "SW68") (pin "1") (pinfunction "1_1") (pintype "unspecified"))
    )
    (net (code "73") (name "Net-(D71-K)") (class "Default")
      (node (ref "D71") (pin "1") (pinfunction "K_1") (pintype "unspecified"))
      (node (ref "SW71") (pin "1") (pinfunction "1_1") (pintype "unspecified"))
    )
    (net (code "74") (name "Net-(D72-K)") (class "Default")
      (node (ref "D72") (pin "1") (pinfunction "K_1") (pintype "unspecified"))
      (node (ref "SW72") (pin "1") (pinfunction "1_1") (pintype "unspecified"))
    )
    (net (code "75") (name "Net-(D73-K)") (class "Default")
      (node (ref "D73") (pin "1") (pinfunction "K_1") (pintype "unspecified"))
      (node (ref "SW73") (pin "1") (pinfunction "1_1") (pintype "unspecified"))
    )
    (net (code "76") (name "Net-(D74-K)") (class "Default")
      (node (ref "D74") (pin "1") (pinfunction "K_1") (pintype "unspecified"))
      (node (ref "SW74") (pin "1") (pinfunction "1_1") (pintype "unspecified"))
    )
    (net (code "77") (name "Net-(D75-K)") (class "Default")
      (node (ref "D75") (pin "1") (pinfunction "K_1") (pintype "unspecified"))
      (node (ref "SW75") (pin "1") (pinfunction "1_1") (pintype "unspecified"))
    )
    (net (code "78") (name "Net-(D76-K)") (class "Default")
      (node (ref "D76") (pin "1") (pinfunction "K_1") (pintype "unspecified"))
      (node (ref "SW76") (pin "1") (pinfunction "1_1") (pintype "unspecified"))
    )
    (net (code "79") (name "Net-(D77-K)") (class "Default")
      (node (ref "D77") (pin "1") (pinfunction "K_1") (pintype "unspecified"))
      (node (ref "SW77") (pin "1") (pinfunction "1_1") (pintype "unspecified"))
    )
    (net (code "80") (name "Net-(D78-K)") (class "Default")
      (node (ref "D78") (pin "1") (pinfunction "K_1") (pintype "unspecified"))
      (node (ref "SW78") (pin "1") (pinfunction "1_1") (pintype "unspecified"))
    )
    (net (code "81") (name "Net-(LED1-C)") (class "Default")
      (node (ref "LED1") (pin "2") (pinfunction "C_2") (pintype "input"))
      (node (ref "R1") (pin "1") (pinfunction "1_1") (pintype "unspecified"))
    )
    (net (code "82") (name "Net-(LED2-C)") (class "Default")
      (node (ref "LED2") (pin "2") (pinfunction "C_2") (pintype "input"))
      (node (ref "R2") (pin "1") (pinfunction "1_1") (pintype "unspecified"))
    )
    (net (code "83") (name "Net-(LED3-C)") (class "Default")
      (node (ref "LED3") (pin "2") (pinfunction "C_2") (pintype "input"))
      (node (ref "R3") (pin "1") (pinfunction "1_1") (pintype "unspecified"))
    )
    (net (code "84") (name "Net-(LED4-C)") (class "Default")
      (node (ref "LED4") (pin "2") (pinfunction "C_2") (pintype "input"))
      (node (ref "R4") (pin "1") (pinfunction "1_1") (pintype "unspecified"))
    )
    (net (code "85") (name "Net-(LED5-C)") (class "Default")
      (node (ref "LED5") (pin "2") (pinfunction "C_2") (pintype "input"))
      (node (ref "R5") (pin "1") (pinfunction "1_1") (pintype "unspecified"))
    )
    (net (code "86") (name "Net-(LED6-C)") (class "Default")
      (node (ref "LED6") (pin "2") (pinfunction "C_2") (pintype "input"))
      (node (ref "R6") (pin "1") (pinfunction "1_1") (pintype "unspecified"))
    )
    (net (code "87") (name "Net-(SW1-Pad4)") (class "Default")
      (node (ref "SW1") (pin "4") (pinfunction "4_4") (pintype "unspecified"))
      (node (ref "SW2") (pin "3") (pinfunction "3_3") (pintype "unspecified"))
    )
    (net (code "88") (name "Net-(SW2-Pad4)") (class "Default")
      (node (ref "SW2") (pin "4") (pinfunction "4_4") (pintype "unspecified"))
      (node (ref "SW3") (pin "3") (pinfunction "3_3") (pintype "unspecified"))
    )
    (net (code "89") (name "Net-(SW3-Pad4)") (class "Default")
      (node (ref "SW3") (pin "4") (pinfunction "4_4") (pintype "unspecified"))
      (node (ref "SW4") (pin "3") (pinfunction "3_3") (pintype "unspecified"))
    )
    (net (code "90") (name "Net-(SW4-Pad4)") (class "Default")
      (node (ref "SW4") (pin "4") (pinfunction "4_4") (pintype "unspecified"))
      (node (ref "SW5") (pin "3") (pinfunction "3_3") (pintype "unspecified"))
    )
    (net (code "91") (name "Net-(SW11-Pad4)") (class "Default")
      (node (ref "SW11") (pin "4") (pinfunction "4_4") (pintype "unspecified"))
      (node (ref "SW12") (pin "3") (pinfunction "3_3") (pintype "unspecified"))
    )
    (net (code "92") (name "Net-(SW12-Pad4)") (class "Default")
      (node (ref "SW12") (pin "4") (pinfunction "4_4") (pintype "unspecified"))
      (node (ref "SW13") (pin "3") (pinfunction "3_3") (pintype "unspecified"))
    )
    (net (code "93") (name "Net-(SW13-Pad4)") (class "Default")
      (node (ref "SW13") (pin "4") (pinfunction "4_4") (pintype "unspecified"))
      (node (ref "SW14") (pin "3") (pinfunction "3_3") (pintype "unspecified"))
    )
    (net (code "94") (name "Net-(SW14-Pad4)") (class "Default")
      (node (ref "SW14") (pin "4") (pinfunction "4_4") (pintype "unspecified"))
      (node (ref "SW15") (pin "3") (pinfunction "3_3") (pintype "unspecified"))
    )
    (net (code "95") (name "Net-(SW15-Pad4)") (class "Default")
      (node (ref "SW15") (pin "4") (pinfunction "4_4") (pintype "unspecified"))
      (node (ref "SW16") (pin "3") (pinfunction "3_3") (pintype "unspecified"))
    )
    (net (code "96") (name "Net-(SW21-Pad4)") (class "Default")
      (node (ref "SW21") (pin "4") (pinfunction "4_4") (pintype "unspecified"))
      (node (ref "SW22") (pin "3") (pinfunction "3_3") (pintype "unspecified"))
    )
    (net (code "97") (name "Net-(SW22-Pad4)") (class "Default")
      (node (ref "SW22") (pin "4") (pinfunction "4_4") (pintype "unspecified"))
      (node (ref "SW23") (pin "3") (pinfunction "3_3") (pintype "unspecified"))
    )
    (net (code "98") (name "Net-(SW23-Pad4)") (class "Default")
      (node (ref "SW23") (pin "4") (pinfunction "4_4") (pintype "unspecified"))
      (node (ref "SW24") (pin "3") (pinfunction "3_3") (pintype "unspecified"))
    )
    (net (code "99") (name "Net-(SW24-Pad4)") (class "Default")
      (node (ref "SW24") (pin "4") (pinfunction "4_4") (pintype "unspecified"))
      (node (ref "SW25") (pin "3") (pinfunction "3_3") (pintype "unspecified"))
    )
    (net (code "100") (name "Net-(SW25-Pad4)") (class "Default")
      (node (ref "SW25") (pin "4") (pinfunction "4_4") (pintype "unspecified"))
      (node (ref "SW26") (pin "3") (pinfunction "3_3") (pintype "unspecified"))
    )
    (net (code "101") (name "Net-(SW31-Pad4)") (class "Default")
      (node (ref "SW31") (pin "4") (pinfunction "4_4") (pintype "unspecified"))
      (node (ref "SW32") (pin "3") (pinfunction "3_3") (pintype "unspecified"))
    )
    (net (code "102") (name "Net-(SW32-Pad4)") (class "Default")
      (node (ref "SW32") (pin "4") (pinfunction "4_4") (pintype "unspecified"))
      (node (ref "SW33") (pin "3") (pinfunction "3_3") (pintype "unspecified"))
    )
    (net (code "103") (name "Net-(SW33-Pad4)") (class "Default")
      (node (ref "SW33") (pin "4") (pinfunction "4_4") (pintype "unspecified"))
      (node (ref "SW34") (pin "3") (pinfunction "3_3") (pintype "unspecified"))
    )
    (net (code "104") (name "Net-(SW34-Pad4)") (class "Default")
      (node (ref "SW34") (pin "4") (pinfunction "4_4") (pintype "unspecified"))
      (node (ref "SW35") (pin "3") (pinfunction "3_3") (pintype "unspecified"))
    )
    (net (code "105") (name "Net-(SW35-Pad4)") (class "Default")
      (node (ref "SW35") (pin "4") (pinfunction "4_4") (pintype "unspecified"))
      (node (ref "SW36") (pin "3") (pinfunction "3_3") (pintype "unspecified"))
    )
    (net (code "106") (name "Net-(SW41-Pad4)") (class "Default")
      (node (ref "SW41") (pin "4") (pinfunction "4_4") (pintype "unspecified"))
      (node (ref "SW42") (pin "3") (pinfunction "3_3") (pintype "unspecified"))
    )
    (net (code "107") (name "Net-(SW42-Pad4)") (class "Default")
      (node (ref "SW42") (pin "4") (pinfunction "4_4") (pintype "unspecified"))
      (node (ref "SW43") (pin "3") (pinfunction "3_3") (pintype "unspecified"))
    )
    (net (code "108") (name "Net-(SW43-Pad4)") (class "Default")
      (node (ref "SW43") (pin "4") (pinfunction "4_4") (pintype "unspecified"))
      (node (ref "SW44") (pin "3") (pinfunction "3_3") (pintype "unspecified"))
    )
    (net (code "109") (name "Net-(SW44-Pad4)") (class "Default")
      (node (ref "SW44") (pin "4") (pinfunction "4_4") (pintype "unspecified"))
      (node (ref "SW45") (pin "3") (pinfunction "3_3") (pintype "unspecified"))
    )
    (net (code "110") (name "Net-(SW45-Pad4)") (class "Default")
      (node (ref "SW45") (pin "4") (pinfunction "4_4") (pintype "unspecified"))
      (node (ref "SW46") (pin "3") (pinfunction "3_3") (pintype "unspecified"))
    )
    (net (code "111") (name "Net-(SW46-Pad4)") (class "Default")
      (node (ref "SW46") (pin "4") (pinfunction "4_4") (pintype "unspecified"))
      (node (ref "SW47") (pin "3") (pinfunction "3_3") (pintype "unspecified"))
    )
    (net (code "112") (name "Net-(SW47-Pad4)") (class "Default")
      (node (ref "SW47") (pin "4") (pinfunction "4_4") (pintype "unspecified"))
      (node (ref "SW48") (pin "3") (pinfunction "3_3") (pintype "unspecified"))
    )
    (net (code "113") (name "Net-(SW51-Pad4)") (class "Default")
      (node (ref "SW51") (pin "4") (pinfunction "4_4") (pintype "unspecified"))
      (node (ref "SW52") (pin "3") (pinfunction "3_3") (pintype "unspecified"))
    )
    (net (code "114") (name "Net-(SW52-Pad4)") (class "Default")
      (node (ref "SW52") (pin "4") (pinfunction "4_4") (pintype "unspecified"))
      (node (ref "SW53") (pin "3") (pinfunction "3_3") (pintype "unspecified"))
    )
    (net (code "115") (name "Net-(SW53-Pad4)") (class "Default")
      (node (ref "SW53") (pin "4") (pinfunction "4_4") (pintype "unspecified"))
      (node (ref "SW54") (pin "3") (pinfunction "3_3") (pintype "unspecified"))
    )
    (net (code "116") (name "Net-(SW54-Pad4)") (class "Default")
      (node (ref "SW54") (pin "4") (pinfunction "4_4") (pintype "unspecified"))
      (node (ref "SW55") (pin "3") (pinfunction "3_3") (pintype "unspecified"))
    )
    (net (code "117") (name "Net-(SW55-Pad4)") (class "Default")
      (node (ref "SW55") (pin "4") (pinfunction "4_4") (pintype "unspecified"))
      (node (ref "SW56") (pin "3") (pinfunction "3_3") (pintype "unspecified"))
    )
    (net (code "118") (name "Net-(SW56-Pad4)") (class "Default")
      (node (ref "SW56") (pin "4") (pinfunction "4_4") (pintype "unspecified"))
      (node (ref "SW57") (pin "3") (pinfunction "3_3") (pintype "unspecified"))
    )
    (net (code "119") (name "Net-(SW57-Pad4)") (class "Default")
      (node (ref "SW57") (pin "4") (pinfunction "4_4") (pintype "unspecified"))
      (node (ref "SW58") (pin "3") (pinfunction "3_3") (pintype "unspecified"))
    )
    (net (code "120") (name "Net-(SW61-Pad4)") (class "Default")
      (node (ref "SW61") (pin "4") (pinfunction "4_4") (pintype "unspecified"))
      (node (ref "SW62") (pin "3") (pinfunction "3_3") (pintype "unspecified"))
    )
    (net (code "121") (name "Net-(SW62-Pad4)") (class "Default")
      (node (ref "SW62") (pin "4") (pinfunction "4_4") (pintype "unspecified"))
      (node (ref "SW63") (pin "3") (pinfunction "3_3") (pintype "unspecified"))
    )
    (net (code "122") (name "Net-(SW63-Pad4)") (class "Default")
      (node (ref "SW63") (pin "4") (pinfunction "4_4") (pintype "unspecified"))
      (node (ref "SW64") (pin "3") (pinfunction "3_3") (pintype "unspecified"))
    )
    (net (code "123") (name "Net-(SW64-Pad4)") (class "Default")
      (node (ref "SW64") (pin "4") (pinfunction "4_4") (pintype "unspecified"))
      (node (ref "SW65") (pin "3") (pinfunction "3_3") (pintype "unspecified"))
    )
    (net (code "124") (name "Net-(SW65-Pad4)") (class "Default")
      (node (ref "SW65") (pin "4") (pinfunction "4_4") (pintype "unspecified"))
      (node (ref "SW66") (pin "3") (pinfunction "3_3") (pintype "unspecified"))
    )
    (net (code "125") (name "Net-(SW66-Pad4)") (class "Default")
      (node (ref "SW66") (pin "4") (pinfunction "4_4") (pintype "unspecified"))
      (node (ref "SW67") (pin "3") (pinfunction "3_3") (pintype "unspecified"))
    )
    (net (code "126") (name "Net-(SW67-Pad4)") (class "Default")
      (node (ref "SW67") (pin "4") (pinfunction "4_4") (pintype "unspecified"))
      (node (ref "SW68") (pin "3") (pinfunction "3_3") (pintype "unspecified"))
    )
    (net (code "127") (name "Net-(SW71-Pad4)") (class "Default")
      (node (ref "SW71") (pin "4") (pinfunction "4_4") (pintype "unspecified"))
      (node (ref "SW72") (pin "3") (pinfunction "3_3") (pintype "unspecified"))
    )
    (net (code "128") (name "Net-(SW72-Pad4)") (class "Default")
      (node (ref "SW72") (pin "4") (pinfunction "4_4") (pintype "unspecified"))
      (node (ref "SW73") (pin "3") (pinfunction "3_3") (pintype "unspecified"))
    )
    (net (code "129") (name "Net-(SW73-Pad4)") (class "Default")
      (node (ref "SW73") (pin "4") (pinfunction "4_4") (pintype "unspecified"))
      (node (ref "SW74") (pin "3") (pinfunction "3_3") (pintype "unspecified"))
    )
    (net (code "130") (name "Net-(SW74-Pad4)") (class "Default")
      (node (ref "SW74") (pin "4") (pinfunction "4_4") (pintype "unspecified"))
      (node (ref "SW75") (pin "3") (pinfunction "3_3") (pintype "unspecified"))
    )
    (net (code "131") (name "Net-(SW75-Pad4)") (class "Default")
      (node (ref "SW75") (pin "4") (pinfunction "4_4") (pintype "unspecified"))
      (node (ref "SW76") (pin "3") (pinfunction "3_3") (pintype "unspecified"))
    )
    (net (code "132") (name "Net-(SW76-Pad4)") (class "Default")
      (node (ref "SW76") (pin "4") (pinfunction "4_4") (pintype "unspecified"))
      (node (ref "SW77") (pin "3") (pinfunction "3_3") (pintype "unspecified"))
    )
    (net (code "133") (name "Net-(SW77-Pad4)") (class "Default")
      (node (ref "SW77") (pin "4") (pinfunction "4_4") (pintype "unspecified"))
      (node (ref "SW78") (pin "3") (pinfunction "3_3") (pintype "unspecified"))
    )
    (net (code "134") (name "Net-(U1-S)") (class "Default")
      (node (ref "R1") (pin "2") (pinfunction "2_2") (pintype "unspecified"))
      (node (ref "U1") (pin "2") (pinfunction "S_2") (pintype "unspecified"))
    )
    (net (code "135") (name "Net-(U2-S)") (class "Default")
      (node (ref "R2") (pin "2") (pinfunction "2_2") (pintype "unspecified"))
      (node (ref "U2") (pin "2") (pinfunction "S_2") (pintype "unspecified"))
    )
    (net (code "136") (name "Net-(U3-S)") (class "Default")
      (node (ref "R3") (pin "2") (pinfunction "2_2") (pintype "unspecified"))
      (node (ref "U3") (pin "2") (pinfunction "S_2") (pintype "unspecified"))
    )
    (net (code "137") (name "Net-(U4-S)") (class "Default")
      (node (ref "R4") (pin "2") (pinfunction "2_2") (pintype "unspecified"))
      (node (ref "U4") (pin "2") (pinfunction "S_2") (pintype "unspecified"))
    )
    (net (code "138") (name "Net-(U5-S)") (class "Default")
      (node (ref "R5") (pin "2") (pinfunction "2_2") (pintype "unspecified"))
      (node (ref "U5") (pin "2") (pinfunction "S_2") (pintype "unspecified"))
    )
    (net (code "139") (name "Net-(U6-S)") (class "Default")
      (node (ref "R6") (pin "2") (pinfunction "2_2") (pintype "unspecified"))
      (node (ref "U6") (pin "2") (pinfunction "S_2") (pintype "unspecified"))
    )
    (net (code "140") (name "VCC") (class "Default")
      (node (ref "CN1") (pin "25") (pinfunction "25_25") (pintype "unspecified"))
      (node (ref "LED1") (pin "1") (pinfunction "A_1") (pintype "input"))
      (node (ref "LED2") (pin "1") (pinfunction "A_1") (pintype "input"))
      (node (ref "LED3") (pin "1") (pinfunction "A_1") (pintype "input"))
      (node (ref "LED4") (pin "1") (pinfunction "A_1") (pintype "input"))
      (node (ref "LED5") (pin "1") (pinfunction "A_1") (pintype "input"))
      (node (ref "LED6") (pin "1") (pinfunction "A_1") (pintype "input"))
      (node (ref "U7") (pin "1") (pinfunction "1_1") (pintype "input"))
    )
    (net (code "141") (name "unconnected-(CN1-Pad24)") (class "Default")
      (node (ref "CN1") (pin "24") (pinfunction "24_24") (pintype "unspecified+no_connect"))
    )
    (net (code "142") (name "unconnected-(SW1-Pad2)") (class "Default")
      (node (ref "SW1") (pin "2") (pinfunction "2_2") (pintype "unspecified"))
    )
    (net (code "143") (name "unconnected-(SW2-Pad2)") (class "Default")
      (node (ref "SW2") (pin "2") (pinfunction "2_2") (pintype "unspecified"))
    )
    (net (code "144") (name "unconnected-(SW3-Pad2)") (class "Default")
      (node (ref "SW3") (pin "2") (pinfunction "2_2") (pintype "unspecified"))
    )
    (net (code "145") (name "unconnected-(SW4-Pad2)") (class "Default")
      (node (ref "SW4") (pin "2") (pinfunction "2_2") (pintype "unspecified"))
    )
    (net (code "146") (name "unconnected-(SW5-Pad2)") (class "Default")
      (node (ref "SW5") (pin "2") (pinfunction "2_2") (pintype "unspecified"))
    )
    (net (code "147") (name "unconnected-(SW5-Pad4)") (class "Default")
      (node (ref "SW5") (pin "4") (pinfunction "4_4") (pintype "unspecified"))
    )
    (net (code "148") (name "unconnected-(SW11-Pad2)") (class "Default")
      (node (ref "SW11") (pin "2") (pinfunction "2_2") (pintype "unspecified"))
    )
    (net (code "149") (name "unconnected-(SW12-Pad2)") (class "Default")
      (node (ref "SW12") (pin "2") (pinfunction "2_2") (pintype "unspecified"))
    )
    (net (code "150") (name "unconnected-(SW13-Pad2)") (class "Default")
      (node (ref "SW13") (pin "2") (pinfunction "2_2") (pintype "unspecified"))
    )
    (net (code "151") (name "unconnected-(SW14-Pad2)") (class "Default")
      (node (ref "SW14") (pin "2") (pinfunction "2_2") (pintype "unspecified"))
    )
    (net (code "152") (name "unconnected-(SW15-Pad2)") (class "Default")
      (node (ref "SW15") (pin "2") (pinfunction "2_2") (pintype "unspecified"))
    )
    (net (code "153") (name "unconnected-(SW16-Pad2)") (class "Default")
      (node (ref "SW16") (pin "2") (pinfunction "2_2") (pintype "unspecified"))
    )
    (net (code "154") (name "unconnected-(SW16-Pad4)") (class "Default")
      (node (ref "SW16") (pin "4") (pinfunction "4_4") (pintype "unspecified"))
    )
    (net (code "155") (name "unconnected-(SW21-Pad2)") (class "Default")
      (node (ref "SW21") (pin "2") (pinfunction "2_2") (pintype "unspecified"))
    )
    (net (code "156") (name "unconnected-(SW22-Pad2)") (class "Default")
      (node (ref "SW22") (pin "2") (pinfunction "2_2") (pintype "unspecified"))
    )
    (net (code "157") (name "unconnected-(SW23-Pad2)") (class "Default")
      (node (ref "SW23") (pin "2") (pinfunction "2_2") (pintype "unspecified"))
    )
    (net (code "158") (name "unconnected-(SW24-Pad2)") (class "Default")
      (node (ref "SW24") (pin "2") (pinfunction "2_2") (pintype "unspecified"))
    )
    (net (code "159") (name "unconnected-(SW25-Pad2)") (class "Default")
      (node (ref "SW25") (pin "2") (pinfunction "2_2") (pintype "unspecified"))
    )
    (net (code "160") (name "unconnected-(SW26-Pad2)") (class "Default")
      (node (ref "SW26") (pin "2") (pinfunction "2_2") (pintype "unspecified"))
    )
    (net (code "161") (name "unconnected-(SW26-Pad4)") (class "Default")
      (node (ref "SW26") (pin "4") (pinfunction "4_4") (pintype "unspecified"))
    )
    (net (code "162") (name "unconnected-(SW31-Pad2)") (class "Default")
      (node (ref "SW31") (pin "2") (pinfunction "2_2") (pintype "unspecified"))
    )
    (net (code "163") (name "unconnected-(SW32-Pad2)") (class "Default")
      (node (ref "SW32") (pin "2") (pinfunction "2_2") (pintype "unspecified"))
    )
    (net (code "164") (name "unconnected-(SW33-Pad2)") (class "Default")
      (node (ref "SW33") (pin "2") (pinfunction "2_2") (pintype "unspecified"))
    )
    (net (code "165") (name "unconnected-(SW34-Pad2)") (class "Default")
      (node (ref "SW34") (pin "2") (pinfunction "2_2") (pintype "unspecified"))
    )
    (net (code "166") (name "unconnected-(SW35-Pad2)") (class "Default")
      (node (ref "SW35") (pin "2") (pinfunction "2_2") (pintype "unspecified"))
    )
    (net (code "167") (name "unconnected-(SW36-Pad2)") (class "Default")
      (node (ref "SW36") (pin "2") (pinfunction "2_2") (pintype "unspecified"))
    )
    (net (code "168") (name "unconnected-(SW36-Pad4)") (class "Default")
      (node (ref "SW36") (pin "4") (pinfunction "4_4") (pintype "unspecified"))
    )
    (net (code "169") (name "unconnected-(SW41-Pad2)") (class "Default")
      (node (ref "SW41") (pin "2") (pinfunction "2_2") (pintype "unspecified"))
    )
    (net (code "170") (name "unconnected-(SW42-Pad2)") (class "Default")
      (node (ref "SW42") (pin "2") (pinfunction "2_2") (pintype "unspecified"))
    )
    (net (code "171") (name "unconnected-(SW43-Pad2)") (class "Default")
      (node (ref "SW43") (pin "2") (pinfunction "2_2") (pintype "unspecified"))
    )
    (net (code "172") (name "unconnected-(SW44-Pad2)") (class "Default")
      (node (ref "SW44") (pin "2") (pinfunction "2_2") (pintype "unspecified"))
    )
    (net (code "173") (name "unconnected-(SW45-Pad2)") (class "Default")
      (node (ref "SW45") (pin "2") (pinfunction "2_2") (pintype "unspecified"))
    )
    (net (code "174") (name "unconnected-(SW46-Pad2)") (class "Default")
      (node (ref "SW46") (pin "2") (pinfunction "2_2") (pintype "unspecified"))
    )
    (net (code "175") (name "unconnected-(SW47-Pad2)") (class "Default")
      (node (ref "SW47") (pin "2") (pinfunction "2_2") (pintype "unspecified"))
    )
    (net (code "176") (name "unconnected-(SW48-Pad2)") (class "Default")
      (node (ref "SW48") (pin "2") (pinfunction "2_2") (pintype "unspecified"))
    )
    (net (code "177") (name "unconnected-(SW48-Pad4)") (class "Default")
      (node (ref "SW48") (pin "4") (pinfunction "4_4") (pintype "unspecified"))
    )
    (net (code "178") (name "unconnected-(SW51-Pad2)") (class "Default")
      (node (ref "SW51") (pin "2") (pinfunction "2_2") (pintype "unspecified"))
    )
    (net (code "179") (name "unconnected-(SW52-Pad2)") (class "Default")
      (node (ref "SW52") (pin "2") (pinfunction "2_2") (pintype "unspecified"))
    )
    (net (code "180") (name "unconnected-(SW53-Pad2)") (class "Default")
      (node (ref "SW53") (pin "2") (pinfunction "2_2") (pintype "unspecified"))
    )
    (net (code "181") (name "unconnected-(SW54-Pad2)") (class "Default")
      (node (ref "SW54") (pin "2") (pinfunction "2_2") (pintype "unspecified"))
    )
    (net (code "182") (name "unconnected-(SW55-Pad2)") (class "Default")
      (node (ref "SW55") (pin "2") (pinfunction "2_2") (pintype "unspecified"))
    )
    (net (code "183") (name "unconnected-(SW56-Pad2)") (class "Default")
      (node (ref "SW56") (pin "2") (pinfunction "2_2") (pintype "unspecified"))
    )
    (net (code "184") (name "unconnected-(SW57-Pad2)") (class "Default")
      (node (ref "SW57") (pin "2") (pinfunction "2_2") (pintype "unspecified"))
    )
    (net (code "185") (name "unconnected-(SW58-Pad2)") (class "Default")
      (node (ref "SW58") (pin "2") (pinfunction "2_2") (pintype "unspecified"))
    )
    (net (code "186") (name "unconnected-(SW58-Pad4)") (class "Default")
      (node (ref "SW58") (pin "4") (pinfunction "4_4") (pintype "unspecified"))
    )
    (net (code "187") (name "unconnected-(SW61-Pad2)") (class "Default")
      (node (ref "SW61") (pin "2") (pinfunction "2_2") (pintype "unspecified"))
    )
    (net (code "188") (name "unconnected-(SW62-Pad2)") (class "Default")
      (node (ref "SW62") (pin "2") (pinfunction "2_2") (pintype "unspecified"))
    )
    (net (code "189") (name "unconnected-(SW63-Pad2)") (class "Default")
      (node (ref "SW63") (pin "2") (pinfunction "2_2") (pintype "unspecified"))
    )
    (net (code "190") (name "unconnected-(SW64-Pad2)") (class "Default")
      (node (ref "SW64") (pin "2") (pinfunction "2_2") (pintype "unspecified"))
    )
    (net (code "191") (name "unconnected-(SW65-Pad2)") (class "Default")
      (node (ref "SW65") (pin "2") (pinfunction "2_2") (pintype "unspecified"))
    )
    (net (code "192") (name "unconnected-(SW66-Pad2)") (class "Default")
      (node (ref "SW66") (pin "2") (pinfunction "2_2") (pintype "unspecified"))
    )
    (net (code "193") (name "unconnected-(SW67-Pad2)") (class "Default")
      (node (ref "SW67") (pin "2") (pinfunction "2_2") (pintype "unspecified"))
    )
    (net (code "194") (name "unconnected-(SW68-Pad2)") (class "Default")
      (node (ref "SW68") (pin "2") (pinfunction "2_2") (pintype "unspecified"))
    )
    (net (code "195") (name "unconnected-(SW68-Pad4)") (class "Default")
      (node (ref "SW68") (pin "4") (pinfunction "4_4") (pintype "unspecified"))
    )
    (net (code "196") (name "unconnected-(SW71-Pad2)") (class "Default")
      (node (ref "SW71") (pin "2") (pinfunction "2_2") (pintype "unspecified"))
    )
    (net (code "197") (name "unconnected-(SW72-Pad2)") (class "Default")
      (node (ref "SW72") (pin "2") (pinfunction "2_2") (pintype "unspecified"))
    )
    (net (code "198") (name "unconnected-(SW73-Pad2)") (class "Default")
      (node (ref "SW73") (pin "2") (pinfunction "2_2") (pintype "unspecified"))
    )
    (net (code "199") (name "unconnected-(SW74-Pad2)") (class "Default")
      (node (ref "SW74") (pin "2") (pinfunction "2_2") (pintype "unspecified"))
    )
    (net (code "200") (name "unconnected-(SW75-Pad2)") (class "Default")
      (node (ref "SW75") (pin "2") (pinfunction "2_2") (pintype "unspecified"))
    )
    (net (code "201") (name "unconnected-(SW76-Pad2)") (class "Default")
      (node (ref "SW76") (pin "2") (pinfunction "2_2") (pintype "unspecified"))
    )
    (net (code "202") (name "unconnected-(SW77-Pad2)") (class "Default")
      (node (ref "SW77") (pin "2") (pinfunction "2_2") (pintype "unspecified"))
    )
    (net (code "203") (name "unconnected-(SW78-Pad2)") (class "Default")
      (node (ref "SW78") (pin "2") (pinfunction "2_2") (pintype "unspecified"))
    )
    (net (code "204") (name "unconnected-(SW78-Pad4)") (class "Default")
      (node (ref "SW78") (pin "4") (pinfunction "4_4") (pintype "unspecified"))
    )
  )
)
